# 2-psg-plain.net
KiCad netlist of a schematic drawn in EAGLE
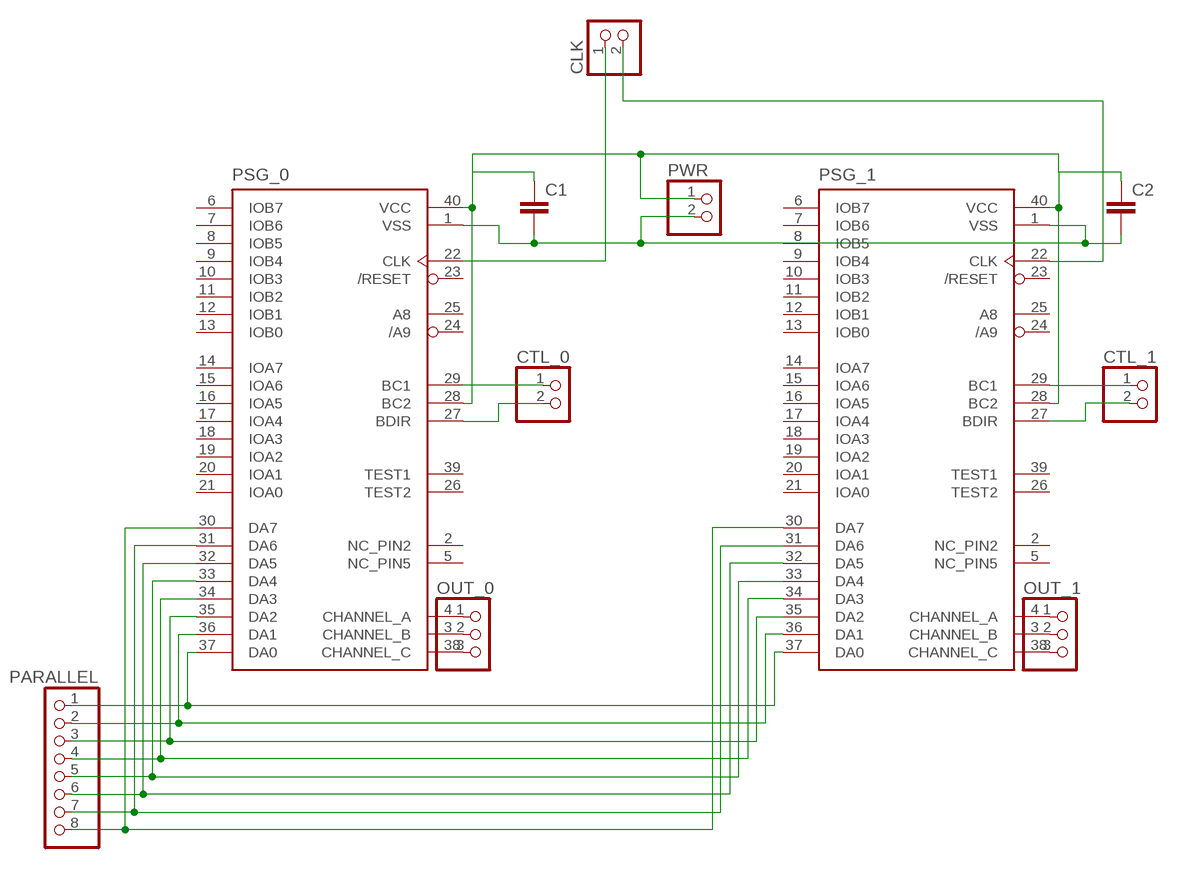
[diagram p0: schematic, sheet 1]

(export (version "E")
  (design (tool "Eeschema 10.0.6"))
  (components
    (comp (ref "C1")
      (value "050X030_0251")
      (footprint "eagle-import:050X030_025")
      (libsource (lib "eagle-import") (part "050X030_0251"))
    )
    (comp (ref "C2")
      (value "050X030_0251")
      (footprint "eagle-import:050X030_025")
      (libsource (lib "eagle-import") (part "050X030_0251"))
    )
    (comp (ref "CLK")
      (value "PINHD-1X2")
      (footprint "eagle-import:1X02")
      (libsource (lib "eagle-import") (part "PINHD-1X2"))
    )
    (comp (ref "CTL_0")
      (value "PINHD-1X2")
      (footprint "eagle-import:1X02")
      (libsource (lib "eagle-import") (part "PINHD-1X2"))
    )
    (comp (ref "CTL_1")
      (value "PINHD-1X2")
      (footprint "eagle-import:1X02")
      (libsource (lib "eagle-import") (part "PINHD-1X2"))
    )
    (comp (ref "OUT_0")
      (value "PINHD-1X3")
      (footprint "eagle-import:1X03")
      (libsource (lib "eagle-import") (part "PINHD-1X3"))
    )
    (comp (ref "OUT_1")
      (value "PINHD-1X3")
      (footprint "eagle-import:1X03")
      (libsource (lib "eagle-import") (part "PINHD-1X3"))
    )
    (comp (ref "PARALLEL")
      (value "PINHD-1X8")
      (footprint "eagle-import:1X08")
      (libsource (lib "eagle-import") (part "PINHD-1X8"))
    )
    (comp (ref "PSG_0")
      (value "AY-3-8910")
      (footprint "eagle-import:DIL40")
      (libsource (lib "eagle-import") (part "AY-3-8910"))
    )
    (comp (ref "PSG_1")
      (value "AY-3-8910")
      (footprint "eagle-import:DIL40")
      (libsource (lib "eagle-import") (part "AY-3-8910"))
    )
    (comp (ref "PWR")
      (value "PINHD-1X2")
      (footprint "eagle-import:1X02")
      (libsource (lib "eagle-import") (part "PINHD-1X2"))
    )
  )
  (nets
    (net (code "1") (name "Net-(PSG_0-BC1)") (class "Default")
      (node (ref "CTL_0") (pin "1") (pinfunction "1_1") (pintype "passive"))
      (node (ref "PSG_0") (pin "29") (pinfunction "BC1_29") (pintype "input"))
    )
    (net (code "2") (name "Net-(PSG_0-BC2)") (class "Default")
      (node (ref "C1") (pin "1") (pinfunction "1_1") (pintype "passive"))
      (node (ref "C2") (pin "1") (pinfunction "1_1") (pintype "passive"))
      (node (ref "PSG_0") (pin "28") (pinfunction "BC2_28") (pintype "input"))
      (node (ref "PSG_0") (pin "40") (pinfunction "VCC_40") (pintype "power_in"))
      (node (ref "PSG_1") (pin "28") (pinfunction "BC2_28") (pintype "input"))
      (node (ref "PSG_1") (pin "40") (pinfunction "VCC_40") (pintype "power_in"))
      (node (ref "PWR") (pin "1") (pinfunction "1_1") (pintype "passive"))
    )
    (net (code "3") (name "Net-(PSG_0-BDIR)") (class "Default")
      (node (ref "CTL_0") (pin "2") (pinfunction "2_2") (pintype "passive"))
      (node (ref "PSG_0") (pin "27") (pinfunction "BDIR_27") (pintype "input"))
    )
    (net (code "4") (name "Net-(PSG_0-CHANNEL_A)") (class "Default")
      (node (ref "OUT_0") (pin "1") (pinfunction "1_1") (pintype "passive"))
      (node (ref "PSG_0") (pin "4") (pinfunction "CHANNEL_A_4") (pintype "output"))
    )
    (net (code "5") (name "Net-(PSG_0-CHANNEL_B)") (class "Default")
      (node (ref "OUT_0") (pin "2") (pinfunction "2_2") (pintype "passive"))
      (node (ref "PSG_0") (pin "3") (pinfunction "CHANNEL_B_3") (pintype "output"))
    )
    (net (code "6") (name "Net-(PSG_0-CHANNEL_C)") (class "Default")
      (node (ref "OUT_0") (pin "3") (pinfunction "3_3") (pintype "passive"))
      (node (ref "PSG_0") (pin "38") (pinfunction "CHANNEL_C_38") (pintype "output"))
    )
    (net (code "7") (name "Net-(PSG_0-CLK)") (class "Default")
      (node (ref "CLK") (pin "1") (pinfunction "1_1") (pintype "passive"))
      (node (ref "PSG_0") (pin "22") (pinfunction "CLK_22") (pintype "input"))
    )
    (net (code "8") (name "Net-(PSG_0-DA0)") (class "Default")
      (node (ref "PARALLEL") (pin "1") (pinfunction "1_1") (pintype "passive"))
      (node (ref "PSG_0") (pin "37") (pinfunction "DA0_37") (pintype "bidirectional"))
      (node (ref "PSG_1") (pin "37") (pinfunction "DA0_37") (pintype "bidirectional"))
    )
    (net (code "9") (name "Net-(PSG_0-DA1)") (class "Default")
      (node (ref "PARALLEL") (pin "2") (pinfunction "2_2") (pintype "passive"))
      (node (ref "PSG_0") (pin "36") (pinfunction "DA1_36") (pintype "bidirectional"))
      (node (ref "PSG_1") (pin "36") (pinfunction "DA1_36") (pintype "bidirectional"))
    )
    (net (code "10") (name "Net-(PSG_0-DA2)") (class "Default")
      (node (ref "PARALLEL") (pin "3") (pinfunction "3_3") (pintype "passive"))
      (node (ref "PSG_0") (pin "35") (pinfunction "DA2_35") (pintype "bidirectional"))
      (node (ref "PSG_1") (pin "35") (pinfunction "DA2_35") (pintype "bidirectional"))
    )
    (net (code "11") (name "Net-(PSG_0-DA3)") (class "Default")
      (node (ref "PARALLEL") (pin "4") (pinfunction "4_4") (pintype "passive"))
      (node (ref "PSG_0") (pin "34") (pinfunction "DA3_34") (pintype "bidirectional"))
      (node (ref "PSG_1") (pin "34") (pinfunction "DA3_34") (pintype "bidirectional"))
    )
    (net (code "12") (name "Net-(PSG_0-DA4)") (class "Default")
      (node (ref "PARALLEL") (pin "5") (pinfunction "5_5") (pintype "passive"))
      (node (ref "PSG_0") (pin "33") (pinfunction "DA4_33") (pintype "bidirectional"))
      (node (ref "PSG_1") (pin "33") (pinfunction "DA4_33") (pintype "bidirectional"))
    )
    (net (code "13") (name "Net-(PSG_0-DA5)") (class "Default")
      (node (ref "PARALLEL") (pin "6") (pinfunction "6_6") (pintype "passive"))
      (node (ref "PSG_0") (pin "32") (pinfunction "DA5_32") (pintype "bidirectional"))
      (node (ref "PSG_1") (pin "32") (pinfunction "DA5_32") (pintype "bidirectional"))
    )
    (net (code "14") (name "Net-(PSG_0-DA6)") (class "Default")
      (node (ref "PARALLEL") (pin "7") (pinfunction "7_7") (pintype "passive"))
      (node (ref "PSG_0") (pin "31") (pinfunction "DA6_31") (pintype "bidirectional"))
      (node (ref "PSG_1") (pin "31") (pinfunction "DA6_31") (pintype "bidirectional"))
    )
    (net (code "15") (name "Net-(PSG_0-DA7)") (class "Default")
      (node (ref "PARALLEL") (pin "8") (pinfunction "8_8") (pintype "passive"))
      (node (ref "PSG_0") (pin "30") (pinfunction "DA7_30") (pintype "bidirectional"))
      (node (ref "PSG_1") (pin "30") (pinfunction "DA7_30") (pintype "bidirectional"))
    )
    (net (code "16") (name "Net-(PSG_0-VSS)") (class "Default")
      (node (ref "C1") (pin "2") (pinfunction "2_2") (pintype "passive"))
      (node (ref "C2") (pin "2") (pinfunction "2_2") (pintype "passive"))
      (node (ref "PSG_0") (pin "1") (pinfunction "VSS_1") (pintype "power_in"))
      (node (ref "PSG_1") (pin "1") (pinfunction "VSS_1") (pintype "power_in"))
      (node (ref "PWR") (pin "2") (pinfunction "2_2") (pintype "passive"))
    )
    (net (code "17") (name "Net-(PSG_1-BC1)") (class "Default")
      (node (ref "CTL_1") (pin "1") (pinfunction "1_1") (pintype "passive"))
      (node (ref "PSG_1") (pin "29") (pinfunction "BC1_29") (pintype "input"))
    )
    (net (code "18") (name "Net-(PSG_1-BDIR)") (class "Default")
      (node (ref "CTL_1") (pin "2") (pinfunction "2_2") (pintype "passive"))
      (node (ref "PSG_1") (pin "27") (pinfunction "BDIR_27") (pintype "input"))
    )
    (net (code "19") (name "Net-(PSG_1-CHANNEL_A)") (class "Default")
      (node (ref "OUT_1") (pin "1") (pinfunction "1_1") (pintype "passive"))
      (node (ref "PSG_1") (pin "4") (pinfunction "CHANNEL_A_4") (pintype "output"))
    )
    (net (code "20") (name "Net-(PSG_1-CHANNEL_B)") (class "Default")
      (node (ref "OUT_1") (pin "2") (pinfunction "2_2") (pintype "passive"))
      (node (ref "PSG_1") (pin "3") (pinfunction "CHANNEL_B_3") (pintype "output"))
    )
    (net (code "21") (name "Net-(PSG_1-CHANNEL_C)") (class "Default")
      (node (ref "OUT_1") (pin "3") (pinfunction "3_3") (pintype "passive"))
      (node (ref "PSG_1") (pin "38") (pinfunction "CHANNEL_C_38") (pintype "output"))
    )
    (net (code "22") (name "Net-(PSG_1-CLK)") (class "Default")
      (node (ref "CLK") (pin "2") (pinfunction "2_2") (pintype "passive"))
      (node (ref "PSG_1") (pin "22") (pinfunction "CLK_22") (pintype "input"))
    )
    (net (code "23") (name "unconnected-(PSG_0-A8-Pad25)") (class "Default")
      (node (ref "PSG_0") (pin "25") (pinfunction "A8_25") (pintype "bidirectional"))
    )
    (net (code "24") (name "unconnected-(PSG_0-IOA0-Pad21)") (class "Default")
      (node (ref "PSG_0") (pin "21") (pinfunction "IOA0_21") (pintype "bidirectional"))
    )
    (net (code "25") (name "unconnected-(PSG_0-IOA1-Pad20)") (class "Default")
      (node (ref "PSG_0") (pin "20") (pinfunction "IOA1_20") (pintype "bidirectional"))
    )
    (net (code "26") (name "unconnected-(PSG_0-IOA2-Pad19)") (class "Default")
      (node (ref "PSG_0") (pin "19") (pinfunction "IOA2_19") (pintype "bidirectional"))
    )
    (net (code "27") (name "unconnected-(PSG_0-IOA3-Pad18)") (class "Default")
      (node (ref "PSG_0") (pin "18") (pinfunction "IOA3_18") (pintype "bidirectional"))
    )
    (net (code "28") (name "unconnected-(PSG_0-IOA4-Pad17)") (class "Default")
      (node (ref "PSG_0") (pin "17") (pinfunction "IOA4_17") (pintype "bidirectional"))
    )
    (net (code "29") (name "unconnected-(PSG_0-IOA5-Pad16)") (class "Default")
      (node (ref "PSG_0") (pin "16") (pinfunction "IOA5_16") (pintype "bidirectional"))
    )
    (net (code "30") (name "unconnected-(PSG_0-IOA6-Pad15)") (class "Default")
      (node (ref "PSG_0") (pin "15") (pinfunction "IOA6_15") (pintype "bidirectional"))
    )
    (net (code "31") (name "unconnected-(PSG_0-IOA7-Pad14)") (class "Default")
      (node (ref "PSG_0") (pin "14") (pinfunction "IOA7_14") (pintype "bidirectional"))
    )
    (net (code "32") (name "unconnected-(PSG_0-IOB0-Pad13)") (class "Default")
      (node (ref "PSG_0") (pin "13") (pinfunction "IOB0_13") (pintype "bidirectional"))
    )
    (net (code "33") (name "unconnected-(PSG_0-IOB1-Pad12)") (class "Default")
      (node (ref "PSG_0") (pin "12") (pinfunction "IOB1_12") (pintype "bidirectional"))
    )
    (net (code "34") (name "unconnected-(PSG_0-IOB2-Pad11)") (class "Default")
      (node (ref "PSG_0") (pin "11") (pinfunction "IOB2_11") (pintype "bidirectional"))
    )
    (net (code "35") (name "unconnected-(PSG_0-IOB3-Pad10)") (class "Default")
      (node (ref "PSG_0") (pin "10") (pinfunction "IOB3_10") (pintype "bidirectional"))
    )
    (net (code "36") (name "unconnected-(PSG_0-IOB4-Pad9)") (class "Default")
      (node (ref "PSG_0") (pin "9") (pinfunction "IOB4_9") (pintype "bidirectional"))
    )
    (net (code "37") (name "unconnected-(PSG_0-IOB5-Pad8)") (class "Default")
      (node (ref "PSG_0") (pin "8") (pinfunction "IOB5_8") (pintype "bidirectional"))
    )
    (net (code "38") (name "unconnected-(PSG_0-IOB6-Pad7)") (class "Default")
      (node (ref "PSG_0") (pin "7") (pinfunction "IOB6_7") (pintype "bidirectional"))
    )
    (net (code "39") (name "unconnected-(PSG_0-IOB7-Pad6)") (class "Default")
      (node (ref "PSG_0") (pin "6") (pinfunction "IOB7_6") (pintype "bidirectional"))
    )
    (net (code "40") (name "unconnected-(PSG_0-NC_PIN2-Pad2)") (class "Default")
      (node (ref "PSG_0") (pin "2") (pinfunction "NC_PIN2_2") (pintype "no_connect"))
    )
    (net (code "41") (name "unconnected-(PSG_0-NC_PIN5-Pad5)") (class "Default")
      (node (ref "PSG_0") (pin "5") (pinfunction "NC_PIN5_5") (pintype "bidirectional"))
    )
    (net (code "42") (name "unconnected-(PSG_0-TEST1-Pad39)") (class "Default")
      (node (ref "PSG_0") (pin "39") (pinfunction "TEST1_39") (pintype "no_connect"))
    )
    (net (code "43") (name "unconnected-(PSG_0-TEST2-Pad26)") (class "Default")
      (node (ref "PSG_0") (pin "26") (pinfunction "TEST2_26") (pintype "no_connect"))
    )
    (net (code "44") (name "unconnected-(PSG_0-{slash}A9-Pad24)") (class "Default")
      (node (ref "PSG_0") (pin "24") (pinfunction "/A9_24") (pintype "bidirectional"))
    )
    (net (code "45") (name "unconnected-(PSG_0-{slash}RESET-Pad23)") (class "Default")
      (node (ref "PSG_0") (pin "23") (pinfunction "/RESET_23") (pintype "input"))
    )
    (net (code "46") (name "unconnected-(PSG_1-A8-Pad25)") (class "Default")
      (node (ref "PSG_1") (pin "25") (pinfunction "A8_25") (pintype "bidirectional"))
    )
    (net (code "47") (name "unconnected-(PSG_1-IOA0-Pad21)") (class "Default")
      (node (ref "PSG_1") (pin "21") (pinfunction "IOA0_21") (pintype "bidirectional"))
    )
    (net (code "48") (name "unconnected-(PSG_1-IOA1-Pad20)") (class "Default")
      (node (ref "PSG_1") (pin "20") (pinfunction "IOA1_20") (pintype "bidirectional"))
    )
    (net (code "49") (name "unconnected-(PSG_1-IOA2-Pad19)") (class "Default")
      (node (ref "PSG_1") (pin "19") (pinfunction "IOA2_19") (pintype "bidirectional"))
    )
    (net (code "50") (name "unconnected-(PSG_1-IOA3-Pad18)") (class "Default")
      (node (ref "PSG_1") (pin "18") (pinfunction "IOA3_18") (pintype "bidirectional"))
    )
    (net (code "51") (name "unconnected-(PSG_1-IOA4-Pad17)") (class "Default")
      (node (ref "PSG_1") (pin "17") (pinfunction "IOA4_17") (pintype "bidirectional"))
    )
    (net (code "52") (name "unconnected-(PSG_1-IOA5-Pad16)") (class "Default")
      (node (ref "PSG_1") (pin "16") (pinfunction "IOA5_16") (pintype "bidirectional"))
    )
    (net (code "53") (name "unconnected-(PSG_1-IOA6-Pad15)") (class "Default")
      (node (ref "PSG_1") (pin "15") (pinfunction "IOA6_15") (pintype "bidirectional"))
    )
    (net (code "54") (name "unconnected-(PSG_1-IOA7-Pad14)") (class "Default")
      (node (ref "PSG_1") (pin "14") (pinfunction "IOA7_14") (pintype "bidirectional"))
    )
    (net (code "55") (name "unconnected-(PSG_1-IOB0-Pad13)") (class "Default")
      (node (ref "PSG_1") (pin "13") (pinfunction "IOB0_13") (pintype "bidirectional"))
    )
    (net (code "56") (name "unconnected-(PSG_1-IOB1-Pad12)") (class "Default")
      (node (ref "PSG_1") (pin "12") (pinfunction "IOB1_12") (pintype "bidirectional"))
    )
    (net (code "57") (name "unconnected-(PSG_1-IOB2-Pad11)") (class "Default")
      (node (ref "PSG_1") (pin "11") (pinfunction "IOB2_11") (pintype "bidirectional"))
    )
    (net (code "58") (name "unconnected-(PSG_1-IOB3-Pad10)") (class "Default")
      (node (ref "PSG_1") (pin "10") (pinfunction "IOB3_10") (pintype "bidirectional"))
    )
    (net (code "59") (name "unconnected-(PSG_1-IOB4-Pad9)") (class "Default")
      (node (ref "PSG_1") (pin "9") (pinfunction "IOB4_9") (pintype "bidirectional"))
    )
    (net (code "60") (name "unconnected-(PSG_1-IOB5-Pad8)") (class "Default")
      (node (ref "PSG_1") (pin "8") (pinfunction "IOB5_8") (pintype "bidirectional"))
    )
    (net (code "61") (name "unconnected-(PSG_1-IOB6-Pad7)") (class "Default")
      (node (ref "PSG_1") (pin "7") (pinfunction "IOB6_7") (pintype "bidirectional"))
    )
    (net (code "62") (name "unconnected-(PSG_1-IOB7-Pad6)") (class "Default")
      (node (ref "PSG_1") (pin "6") (pinfunction "IOB7_6") (pintype "bidirectional"))
    )
    (net (code "63") (name "unconnected-(PSG_1-NC_PIN2-Pad2)") (class "Default")
      (node (ref "PSG_1") (pin "2") (pinfunction "NC_PIN2_2") (pintype "no_connect"))
    )
    (net (code "64") (name "unconnected-(PSG_1-NC_PIN5-Pad5)") (class "Default")
      (node (ref "PSG_1") (pin "5") (pinfunction "NC_PIN5_5") (pintype "bidirectional"))
    )
    (net (code "65") (name "unconnected-(PSG_1-TEST1-Pad39)") (class "Default")
      (node (ref "PSG_1") (pin "39") (pinfunction "TEST1_39") (pintype "no_connect"))
    )
    (net (code "66") (name "unconnected-(PSG_1-TEST2-Pad26)") (class "Default")
      (node (ref "PSG_1") (pin "26") (pinfunction "TEST2_26") (pintype "no_connect"))
    )
    (net (code "67") (name "unconnected-(PSG_1-{slash}A9-Pad24)") (class "Default")
      (node (ref "PSG_1") (pin "24") (pinfunction "/A9_24") (pintype "bidirectional"))
    )
    (net (code "68") (name "unconnected-(PSG_1-{slash}RESET-Pad23)") (class "Default")
      (node (ref "PSG_1") (pin "23") (pinfunction "/RESET_23") (pintype "input"))
    )
  )
)
